# Hbridge0.net
KiCad netlist of a schematic drawn in Altium Designer
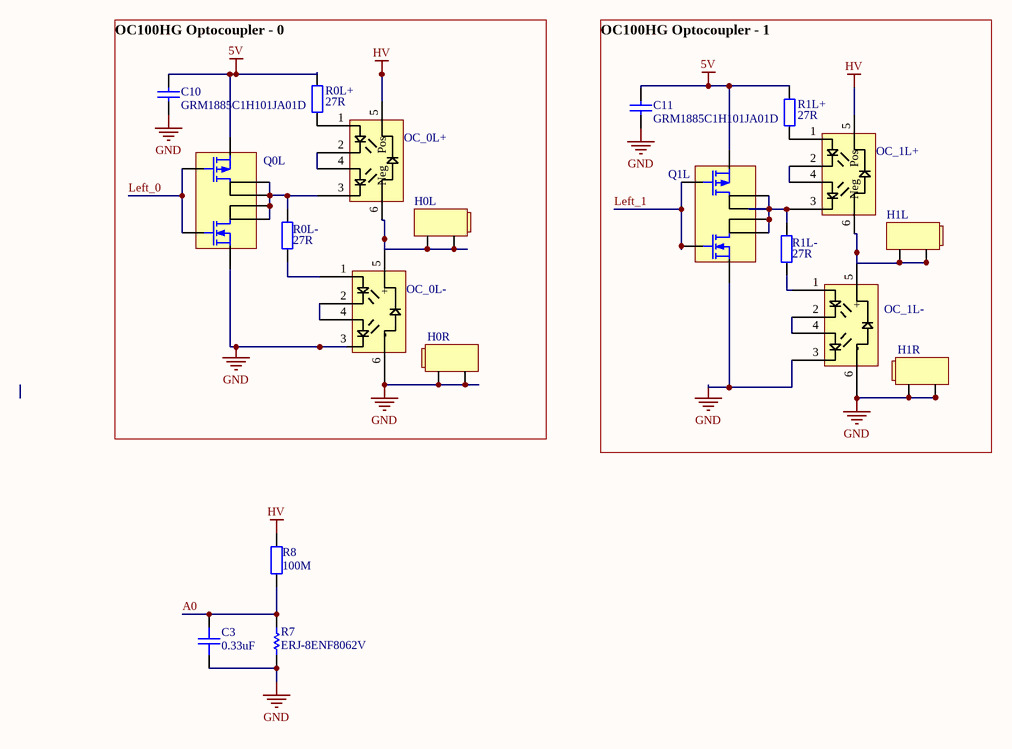
[diagram p0: Hbridge0.SchDoc]

(export (version "E")
  (design (tool "Eeschema 10.0.6"))
  (components
    (comp (ref "C3")
      (value "0.33uF")
      (footprint "1206 CAP")
      (description "‎399-1285-1-ND‎ Manufacturer: ‎C1206C334K3RACTU‎")
      (fields (field (name "Comment") "Capacitor 0.33uF"))
      (libsource (lib "Schlib") (part "Capacitor 0.33uF"))
    )
    (comp (ref "C10")
      (value "GRM1885C1H101JA01D")
      (footprint "CAPC1608X90X35NL10T15")
      (fields (field (name "MANUFACTURER") "Murata"))
      (libsource (lib "Altium Content Vault") (part "CAP"))
    )
    (comp (ref "C11")
      (value "GRM1885C1H101JA01D")
      (footprint "CAPC1608X90X35NL10T15")
      (fields (field (name "MANUFACTURER") "Murata"))
      (libsource (lib "Altium Content Vault") (part "CAP"))
    )
    (comp (ref "H0L")
      (value "HV Socket")
      (footprint "HV Socket 2mm")
      (description "Black: 486-3654-ND\r\nRed: ‎486-3655-ND‎")
      (libsource (lib "") (part "HV Socket_1"))
    )
    (comp (ref "H0R")
      (value "HV Socket")
      (footprint "HV Socket 2mm")
      (description "Black: 486-3654-ND\r\nRed: ‎486-3655-ND‎")
      (libsource (lib "Schlib") (part "HV Socket"))
    )
    (comp (ref "H1L")
      (value "HV Socket")
      (footprint "HV Socket 2mm")
      (description "Black: 486-3654-ND\r\nRed: ‎486-3655-ND‎")
      (libsource (lib "") (part "HV Socket_1"))
    )
    (comp (ref "H1R")
      (value "HV Socket")
      (footprint "HV Socket 2mm")
      (description "Black: 486-3654-ND\r\nRed: ‎486-3655-ND‎")
      (libsource (lib "Schlib") (part "HV Socket"))
    )
    (comp (ref "OC_0L+") (value "OC100HG") (footprint "OC100G") (libsource (lib "Schlib1") (part "OC100HG")))
    (comp (ref "OC_0L-") (value "OC100HG") (footprint "OC100G") (libsource (lib "") (part "OC100HG_1")))
    (comp (ref "OC_1L+") (value "OC100HG") (footprint "OC100G") (libsource (lib "Schlib1") (part "OC100HG")))
    (comp (ref "OC_1L-") (value "OC100HG") (footprint "OC100G") (libsource (lib "") (part "OC100HG_1")))
    (comp (ref "Q0L")
      (value "Dual MOSFET")
      (footprint "SO-8")
      (libsource (lib "Schlib") (part "Dual MOSFET"))
    )
    (comp (ref "Q1L")
      (value "Dual MOSFET")
      (footprint "SO-8")
      (libsource (lib "Schlib") (part "Dual MOSFET"))
    )
    (comp (ref "R0L+")
      (value "27R")
      (footprint "1206 R")
      (description "Manufacturer ‎HRG3216Q-27R0-D-T1‎\r\nDigikey ‎408-1908-1-ND")
      (fields (field (name "Comment") "Resistor"))
      (libsource (lib "") (part "Resistor 27R_1"))
    )
    (comp (ref "R0L-")
      (value "27R")
      (footprint "1206 R")
      (description "Manufacturer ‎HRG3216Q-27R0-D-T1‎\r\nDigikey ‎408-1908-1-ND")
      (fields (field (name "Comment") "Resistor"))
      (libsource (lib "Schlib") (part "Resistor 27R"))
    )
    (comp (ref "R1L+")
      (value "27R")
      (footprint "1206 R")
      (description "Manufacturer ‎HRG3216Q-27R0-D-T1‎\r\nDigikey ‎408-1908-1-ND")
      (fields (field (name "Comment") "Resistor"))
      (libsource (lib "") (part "Resistor 27R_1"))
    )
    (comp (ref "R1L-")
      (value "27R")
      (footprint "1206 R")
      (description "Manufacturer ‎HRG3216Q-27R0-D-T1‎\r\nDigikey ‎408-1908-1-ND")
      (fields (field (name "Comment") "Resistor"))
      (libsource (lib "Schlib") (part "Resistor 27R"))
    )
    (comp (ref "R7")
      (value "ERJ-8ENF8062V")
      (footprint "RESC3216X70X50LL05T20")
      (fields (field (name "MANUFACTURER") "Panasonic"))
      (libsource (lib "Altium Content Vault") (part "RES"))
    )
    (comp (ref "R8")
      (value "100M")
      (footprint "HV resistor")
      (description "Digikey:‎SM102031006FE-ND‎\r\nManufacturer: ‎SM102031006FE-ND‎")
      (fields (field (name "Comment") "Resistor"))
      (libsource (lib "Schlib") (part "Resistor 100M"))
    )
  )
  (nets
    (net (code "1") (name "/A0") (class "Default")
      (node (ref "C3") (pin "2") (pinfunction "2_2") (pintype "passive"))
      (node (ref "R7") (pin "2") (pinfunction "2_2") (pintype "passive"))
      (node (ref "R8") (pin "1") (pinfunction "1_1") (pintype "passive"))
    )
    (net (code "2") (name "/Left_0") (class "Default")
      (node (ref "Q0L") (pin "2") (pinfunction "2_2") (pintype "passive"))
      (node (ref "Q0L") (pin "4") (pinfunction "4_4") (pintype "passive"))
    )
    (net (code "3") (name "/Left_1") (class "Default")
      (node (ref "Q1L") (pin "2") (pinfunction "2_2") (pintype "passive"))
      (node (ref "Q1L") (pin "4") (pinfunction "4_4") (pintype "passive"))
    )
    (net (code "4") (name "5V") (class "Default")
      (node (ref "C10") (pin "2") (pinfunction "2_2") (pintype "passive"))
      (node (ref "C11") (pin "2") (pinfunction "2_2") (pintype "passive"))
      (node (ref "Q0L") (pin "3") (pinfunction "3_3") (pintype "passive"))
      (node (ref "Q1L") (pin "3") (pinfunction "3_3") (pintype "passive"))
      (node (ref "R0L+") (pin "2") (pinfunction "2_2") (pintype "passive"))
      (node (ref "R1L+") (pin "2") (pinfunction "2_2") (pintype "passive"))
    )
    (net (code "5") (name "GND") (class "Default")
      (node (ref "C10") (pin "1") (pinfunction "1_1") (pintype "passive"))
      (node (ref "C11") (pin "1") (pinfunction "1_1") (pintype "passive"))
      (node (ref "C3") (pin "1") (pinfunction "1_1") (pintype "passive"))
      (node (ref "H0R") (pin "1") (pinfunction "1_1") (pintype "passive"))
      (node (ref "H0R") (pin "2") (pinfunction "2_2") (pintype "passive"))
      (node (ref "H1R") (pin "1") (pinfunction "1_1") (pintype "passive"))
      (node (ref "H1R") (pin "2") (pinfunction "2_2") (pintype "passive"))
      (node (ref "OC_0L-") (pin "3") (pinfunction "LED_2-_3") (pintype "passive"))
      (node (ref "OC_0L-") (pin "6") (pinfunction "-_6") (pintype "passive"))
      (node (ref "OC_1L-") (pin "3") (pinfunction "LED_2-_3") (pintype "passive"))
      (node (ref "OC_1L-") (pin "6") (pinfunction "-_6") (pintype "passive"))
      (node (ref "Q0L") (pin "1") (pinfunction "1_1") (pintype "passive"))
      (node (ref "Q1L") (pin "1") (pinfunction "1_1") (pintype "passive"))
      (node (ref "R7") (pin "1") (pinfunction "1_1") (pintype "passive"))
    )
    (net (code "6") (name "HV") (class "Default")
      (node (ref "OC_0L+") (pin "5") (pinfunction "Pos_5") (pintype "passive"))
      (node (ref "OC_1L+") (pin "5") (pinfunction "Pos_5") (pintype "passive"))
      (node (ref "R8") (pin "2") (pinfunction "2_2") (pintype "passive"))
    )
    (net (code "7") (name "Net-(OC_0L+-LED_1+)") (class "Default")
      (node (ref "OC_0L+") (pin "1") (pinfunction "LED_1+_1") (pintype "passive"))
      (node (ref "R0L+") (pin "1") (pinfunction "1_1") (pintype "passive"))
    )
    (net (code "8") (name "Net-(OC_0L+-LED_1-)") (class "Default")
      (node (ref "OC_0L+") (pin "2") (pinfunction "LED_1-_2") (pintype "passive"))
      (node (ref "OC_0L+") (pin "4") (pinfunction "LED_2+_4") (pintype "passive"))
    )
    (net (code "9") (name "Net-(OC_0L+-LED_2-)") (class "Default")
      (node (ref "OC_0L+") (pin "3") (pinfunction "LED_2-_3") (pintype "passive"))
      (node (ref "Q0L") (pin "5") (pinfunction "5_5") (pintype "passive"))
      (node (ref "Q0L") (pin "6") (pinfunction "6_6") (pintype "passive"))
      (node (ref "Q0L") (pin "7") (pinfunction "7_7") (pintype "passive"))
      (node (ref "Q0L") (pin "8") (pinfunction "8_8") (pintype "passive"))
      (node (ref "R0L-") (pin "1") (pinfunction "1_1") (pintype "passive"))
    )
    (net (code "10") (name "Net-(OC_0L+-Neg)") (class "Default")
      (node (ref "H0L") (pin "1") (pinfunction "1_1") (pintype "passive"))
      (node (ref "H0L") (pin "2") (pinfunction "2_2") (pintype "passive"))
      (node (ref "OC_0L+") (pin "6") (pinfunction "Neg_6") (pintype "passive"))
      (node (ref "OC_0L-") (pin "5") (pinfunction "+_5") (pintype "passive"))
    )
    (net (code "11") (name "Net-(OC_0L--LED_1+)") (class "Default")
      (node (ref "OC_0L-") (pin "1") (pinfunction "LED_1+_1") (pintype "passive"))
      (node (ref "R0L-") (pin "2") (pinfunction "2_2") (pintype "passive"))
    )
    (net (code "12") (name "Net-(OC_0L--LED_1-)") (class "Default")
      (node (ref "OC_0L-") (pin "2") (pinfunction "LED_1-_2") (pintype "passive"))
      (node (ref "OC_0L-") (pin "4") (pinfunction "LED_2+_4") (pintype "passive"))
    )
    (net (code "13") (name "Net-(OC_1L+-LED_1+)") (class "Default")
      (node (ref "OC_1L+") (pin "1") (pinfunction "LED_1+_1") (pintype "passive"))
      (node (ref "R1L+") (pin "1") (pinfunction "1_1") (pintype "passive"))
    )
    (net (code "14") (name "Net-(OC_1L+-LED_1-)") (class "Default")
      (node (ref "OC_1L+") (pin "2") (pinfunction "LED_1-_2") (pintype "passive"))
      (node (ref "OC_1L+") (pin "4") (pinfunction "LED_2+_4") (pintype "passive"))
    )
    (net (code "15") (name "Net-(OC_1L+-LED_2-)") (class "Default")
      (node (ref "OC_1L+") (pin "3") (pinfunction "LED_2-_3") (pintype "passive"))
      (node (ref "Q1L") (pin "5") (pinfunction "5_5") (pintype "passive"))
      (node (ref "Q1L") (pin "6") (pinfunction "6_6") (pintype "passive"))
      (node (ref "Q1L") (pin "7") (pinfunction "7_7") (pintype "passive"))
      (node (ref "Q1L") (pin "8") (pinfunction "8_8") (pintype "passive"))
      (node (ref "R1L-") (pin "1") (pinfunction "1_1") (pintype "passive"))
    )
    (net (code "16") (name "Net-(OC_1L+-Neg)") (class "Default")
      (node (ref "H1L") (pin "1") (pinfunction "1_1") (pintype "passive"))
      (node (ref "H1L") (pin "2") (pinfunction "2_2") (pintype "passive"))
      (node (ref "OC_1L+") (pin "6") (pinfunction "Neg_6") (pintype "passive"))
      (node (ref "OC_1L-") (pin "5") (pinfunction "+_5") (pintype "passive"))
    )
    (net (code "17") (name "Net-(OC_1L--LED_1+)") (class "Default")
      (node (ref "OC_1L-") (pin "1") (pinfunction "LED_1+_1") (pintype "passive"))
      (node (ref "R1L-") (pin "2") (pinfunction "2_2") (pintype "passive"))
    )
    (net (code "18") (name "Net-(OC_1L--LED_1-)") (class "Default")
      (node (ref "OC_1L-") (pin "2") (pinfunction "LED_1-_2") (pintype "passive"))
      (node (ref "OC_1L-") (pin "4") (pinfunction "LED_2+_4") (pintype "passive"))
    )
  )
)
